# line_follower.net
KiCad netlist of a schematic drawn in EAGLE
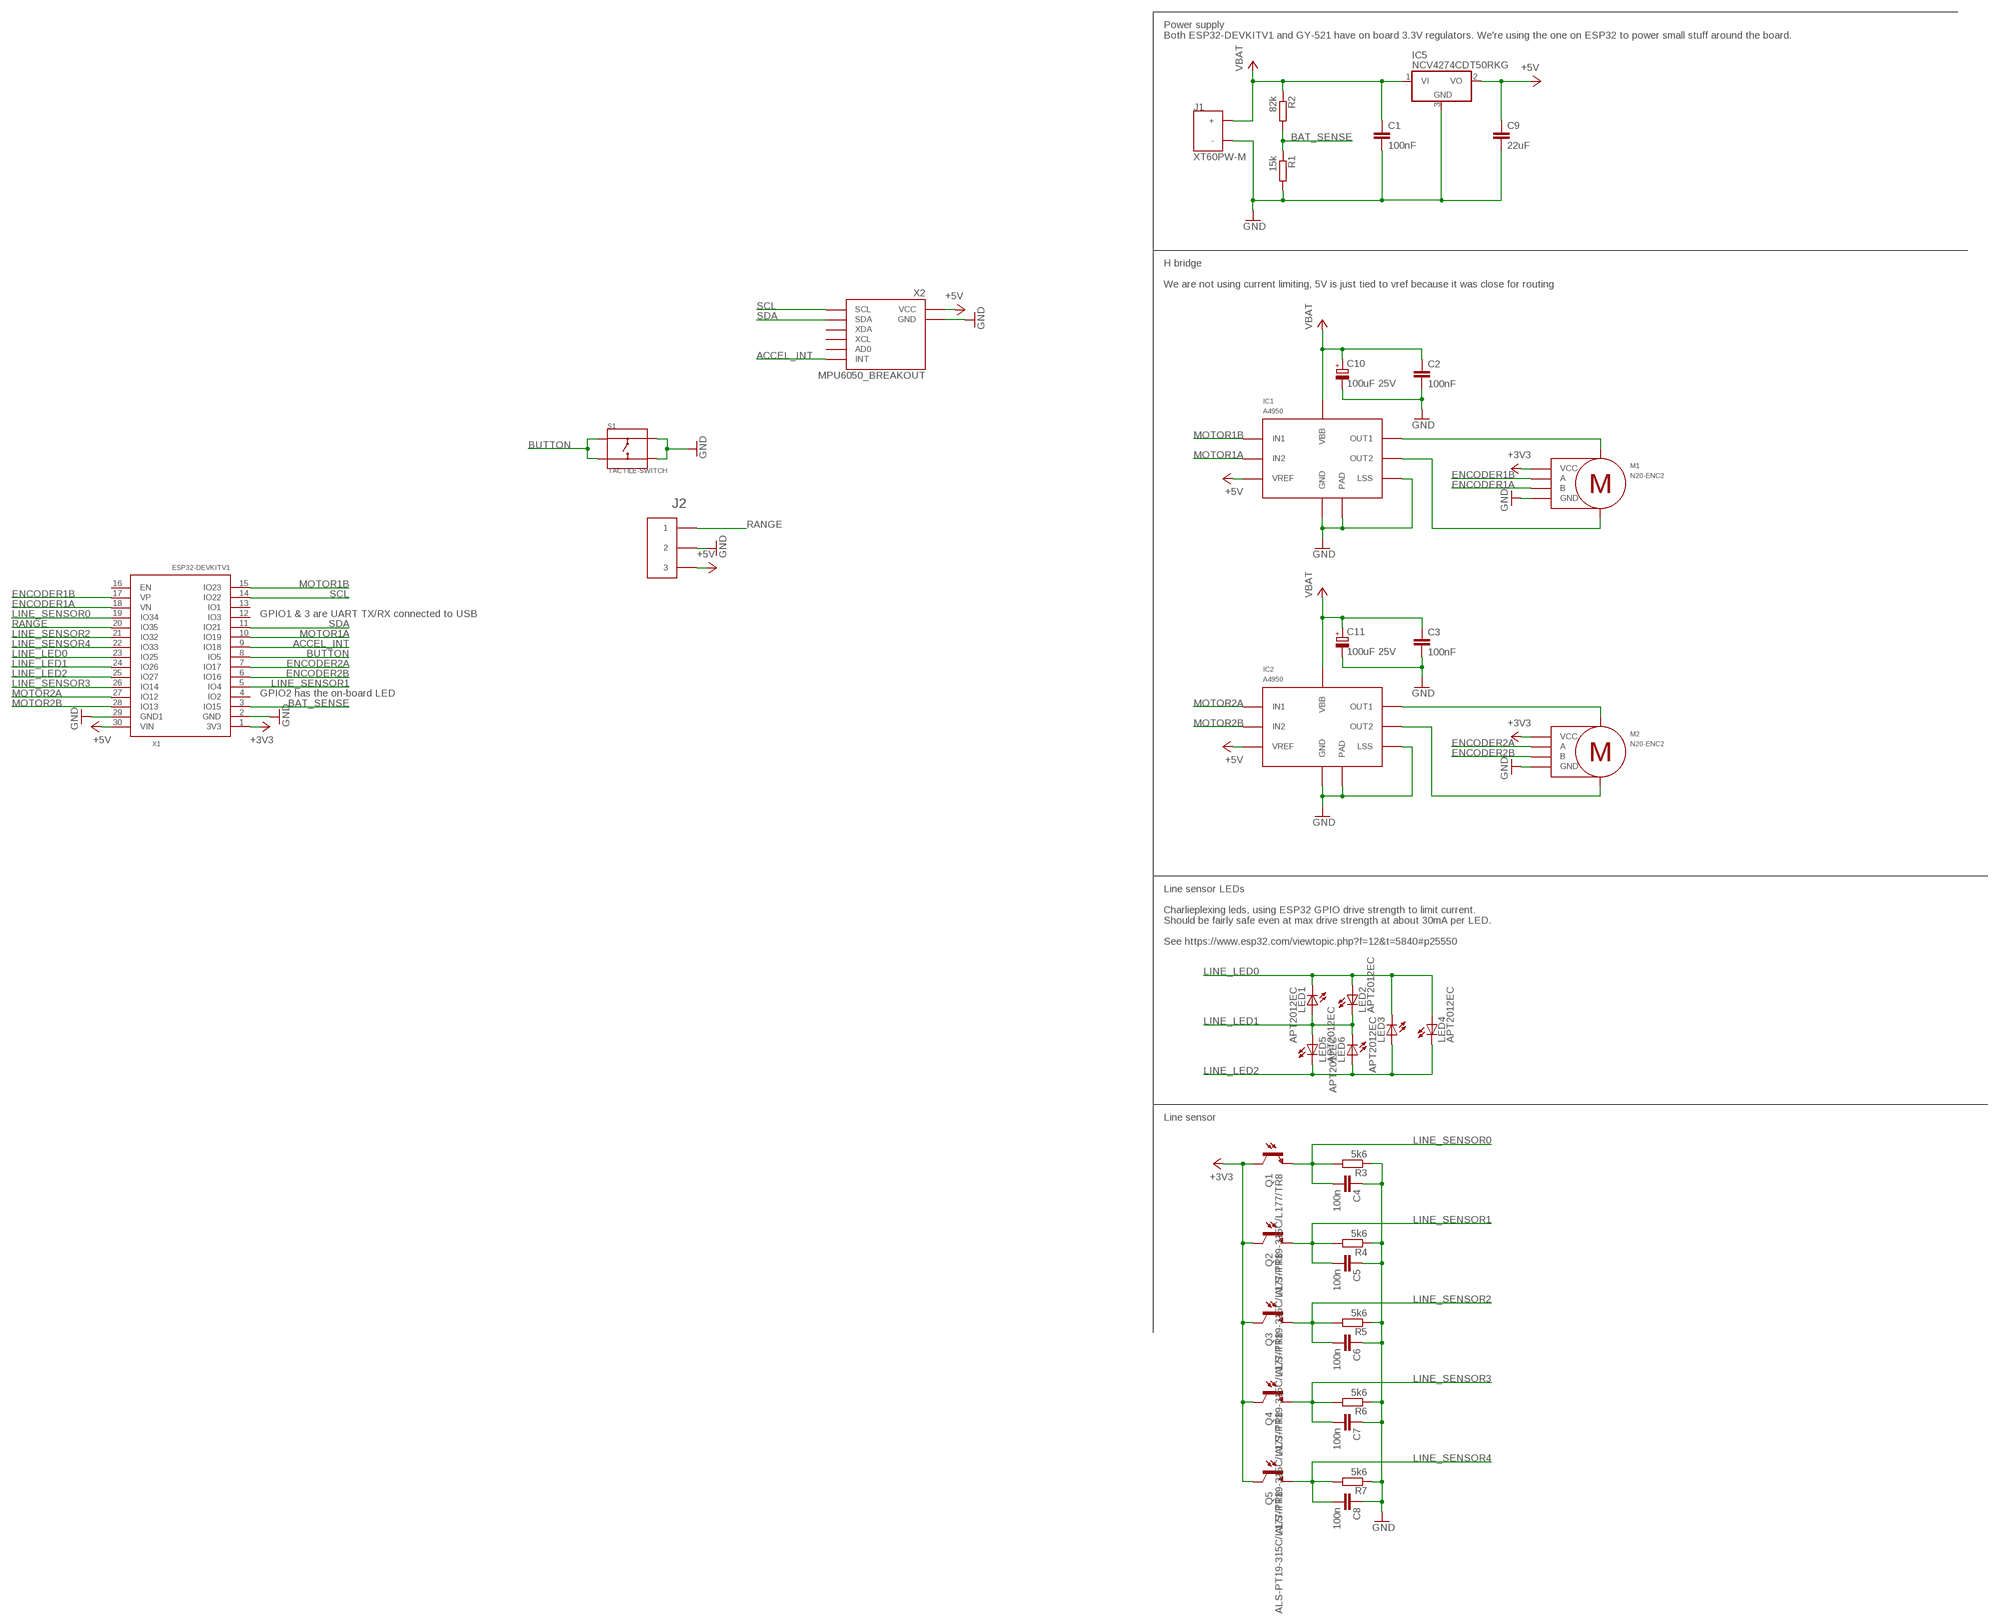
[diagram p0: schematic, sheet 1]

(export (version "E")
  (design (tool "Eeschema 10.0.6"))
  (components
    (comp (ref "C1")
      (value "100nF")
      (footprint "eagle-import:C0805")
      (libsource (lib "eagle-import") (part "C-EUC0805"))
    )
    (comp (ref "C2")
      (value "100nF")
      (footprint "eagle-import:C0805")
      (libsource (lib "eagle-import") (part "C-EUC0805"))
    )
    (comp (ref "C3")
      (value "100nF")
      (footprint "eagle-import:C0805")
      (libsource (lib "eagle-import") (part "C-EUC0805"))
    )
    (comp (ref "C4")
      (value "100n")
      (footprint "eagle-import:C0805")
      (libsource (lib "eagle-import") (part "C-EUC0805"))
    )
    (comp (ref "C5")
      (value "100n")
      (footprint "eagle-import:C0805")
      (libsource (lib "eagle-import") (part "C-EUC0805"))
    )
    (comp (ref "C6")
      (value "100n")
      (footprint "eagle-import:C0805")
      (libsource (lib "eagle-import") (part "C-EUC0805"))
    )
    (comp (ref "C7")
      (value "100n")
      (footprint "eagle-import:C0805")
      (libsource (lib "eagle-import") (part "C-EUC0805"))
    )
    (comp (ref "C8")
      (value "100n")
      (footprint "eagle-import:C0805")
      (libsource (lib "eagle-import") (part "C-EUC0805"))
    )
    (comp (ref "C9")
      (value "22uF")
      (footprint "eagle-import:C0805")
      (libsource (lib "eagle-import") (part "C-EUC0805"))
    )
    (comp (ref "C10")
      (value "100uF 25V")
      (footprint "eagle-import:UD-6,3X5,8_NICHICON")
      (libsource (lib "eagle-import") (part "CPOL-EUUD-6,3X8,8"))
    )
    (comp (ref "C11")
      (value "100uF 25V")
      (footprint "eagle-import:UD-6,3X5,8_NICHICON")
      (libsource (lib "eagle-import") (part "CPOL-EUUD-6,3X8,8"))
    )
    (comp (ref "IC1")
      (value "A4950")
      (footprint "eagle-import:SOIC8_PAD")
      (libsource (lib "eagle-import") (part "A4950"))
    )
    (comp (ref "IC2")
      (value "A4950")
      (footprint "eagle-import:SOIC8_PAD")
      (libsource (lib "eagle-import") (part "A4950"))
    )
    (comp (ref "IC5")
      (value "NCV4274CDT50RKG")
      (footprint "eagle-import:TO252")
      (libsource (lib "eagle-import") (part "78DT05"))
    )
    (comp (ref "J1")
      (value "XT60PW-M")
      (footprint "eagle-import:XT60PW-M")
      (libsource (lib "eagle-import") (part "XT60PW-M"))
    )
    (comp (ref "J2")
      (value "2.54MM_HEADER_3X1")
      (footprint "eagle-import:2.54MM_HEADER_3X1")
      (libsource (lib "eagle-import") (part "2.54MM_HEADER_3X1"))
    )
    (comp (ref "LED1")
      (value "APT2012EC")
      (footprint "eagle-import:CHIP-LED0805")
      (libsource (lib "eagle-import") (part "LEDCHIP-LED0805"))
    )
    (comp (ref "LED2")
      (value "APT2012EC")
      (footprint "eagle-import:CHIP-LED0805")
      (libsource (lib "eagle-import") (part "LEDCHIP-LED0805"))
    )
    (comp (ref "LED3")
      (value "APT2012EC")
      (footprint "eagle-import:CHIP-LED0805")
      (libsource (lib "eagle-import") (part "LEDCHIP-LED0805"))
    )
    (comp (ref "LED4")
      (value "APT2012EC")
      (footprint "eagle-import:CHIP-LED0805")
      (libsource (lib "eagle-import") (part "LEDCHIP-LED0805"))
    )
    (comp (ref "LED5")
      (value "APT2012EC")
      (footprint "eagle-import:CHIP-LED0805")
      (libsource (lib "eagle-import") (part "LEDCHIP-LED0805"))
    )
    (comp (ref "LED6")
      (value "APT2012EC")
      (footprint "eagle-import:CHIP-LED0805")
      (libsource (lib "eagle-import") (part "LEDCHIP-LED0805"))
    )
    (comp (ref "M1")
      (value "N20-ENC2")
      (footprint "eagle-import:2.54MM_HEADER_6X1")
      (libsource (lib "eagle-import") (part "N20-ENC2"))
    )
    (comp (ref "M2")
      (value "N20-ENC2")
      (footprint "eagle-import:2.54MM_HEADER_6X1")
      (libsource (lib "eagle-import") (part "N20-ENC2"))
    )
    (comp (ref "Q1")
      (value "ALS-PT19-315C/L177/TR8")
      (footprint "eagle-import:PHOTOTRANSISTOR-1.7MM")
      (libsource (lib "eagle-import") (part "ALS-PT19-315C/L177/TR8"))
    )
    (comp (ref "Q2")
      (value "ALS-PT19-315C/L177/TR8")
      (footprint "eagle-import:PHOTOTRANSISTOR-1.7MM")
      (libsource (lib "eagle-import") (part "ALS-PT19-315C/L177/TR8"))
    )
    (comp (ref "Q3")
      (value "ALS-PT19-315C/L177/TR8")
      (footprint "eagle-import:PHOTOTRANSISTOR-1.7MM")
      (libsource (lib "eagle-import") (part "ALS-PT19-315C/L177/TR8"))
    )
    (comp (ref "Q4")
      (value "ALS-PT19-315C/L177/TR8")
      (footprint "eagle-import:PHOTOTRANSISTOR-1.7MM")
      (libsource (lib "eagle-import") (part "ALS-PT19-315C/L177/TR8"))
    )
    (comp (ref "Q5")
      (value "ALS-PT19-315C/L177/TR8")
      (footprint "eagle-import:PHOTOTRANSISTOR-1.7MM")
      (libsource (lib "eagle-import") (part "ALS-PT19-315C/L177/TR8"))
    )
    (comp (ref "R1")
      (value "15k")
      (footprint "eagle-import:R0805")
      (libsource (lib "eagle-import") (part "R-EU_R0805"))
    )
    (comp (ref "R2")
      (value "82k")
      (footprint "eagle-import:R0805")
      (libsource (lib "eagle-import") (part "R-EU_R0805"))
    )
    (comp (ref "R3")
      (value "5k6")
      (footprint "eagle-import:R0805")
      (libsource (lib "eagle-import") (part "R-EU_R0805"))
    )
    (comp (ref "R4")
      (value "5k6")
      (footprint "eagle-import:R0805")
      (libsource (lib "eagle-import") (part "R-EU_R0805"))
    )
    (comp (ref "R5")
      (value "5k6")
      (footprint "eagle-import:R0805")
      (libsource (lib "eagle-import") (part "R-EU_R0805"))
    )
    (comp (ref "R6")
      (value "5k6")
      (footprint "eagle-import:R0805")
      (libsource (lib "eagle-import") (part "R-EU_R0805"))
    )
    (comp (ref "R7")
      (value "5k6")
      (footprint "eagle-import:R0805")
      (libsource (lib "eagle-import") (part "R-EU_R0805"))
    )
    (comp (ref "S1")
      (value "TACTILE-SWITCH")
      (footprint "eagle-import:SW4-SMD-4.5MM")
      (libsource (lib "eagle-import") (part "TACTILE-SWITCH"))
    )
    (comp (ref "X1")
      (value "ESP32DEVKITV1")
      (footprint "eagle-import:ESP32-DEVKITV1")
      (libsource (lib "eagle-import") (part "ESP32DEVKITV1"))
    )
    (comp (ref "X2")
      (value "MPU6050_BREAKOUT")
      (footprint "eagle-import:MPU6050_BREAKOUT")
      (libsource (lib "eagle-import") (part "MPU6050_BREAKOUT"))
    )
  )
  (nets
    (net (code "1") (name "+3V3") (class "Default")
      (node (ref "M1") (pin "P$5") (pinfunction "VCC_P$5") (pintype "power_in"))
      (node (ref "M2") (pin "P$5") (pinfunction "VCC_P$5") (pintype "power_in"))
      (node (ref "Q1") (pin "C") (pinfunction "C_C") (pintype "passive"))
      (node (ref "Q2") (pin "C") (pinfunction "C_C") (pintype "passive"))
      (node (ref "Q3") (pin "C") (pinfunction "C_C") (pintype "passive"))
      (node (ref "Q4") (pin "C") (pinfunction "C_C") (pintype "passive"))
      (node (ref "Q5") (pin "C") (pinfunction "C_C") (pintype "passive"))
      (node (ref "X1") (pin "1") (pinfunction "3V3_1") (pintype "bidirectional"))
    )
    (net (code "2") (name "+5V") (class "Default")
      (node (ref "C9") (pin "1") (pinfunction "1_1") (pintype "passive"))
      (node (ref "IC1") (pin "4") (pinfunction "VREF_4") (pintype "bidirectional"))
      (node (ref "IC2") (pin "4") (pinfunction "VREF_4") (pintype "bidirectional"))
      (node (ref "IC5") (pin "2") (pinfunction "VO_2") (pintype "passive"))
      (node (ref "J2") (pin "P$3") (pinfunction "3_P$3") (pintype "bidirectional"))
      (node (ref "X1") (pin "30") (pinfunction "VIN_30") (pintype "bidirectional"))
      (node (ref "X2") (pin "P$1") (pinfunction "VCC_P$1") (pintype "power_in"))
    )
    (net (code "3") (name "/ACCEL_INT") (class "Default")
      (node (ref "X1") (pin "9") (pinfunction "IO18_9") (pintype "bidirectional"))
      (node (ref "X2") (pin "P$8") (pinfunction "INT_P$8") (pintype "bidirectional"))
    )
    (net (code "4") (name "/BAT_SENSE") (class "Default")
      (node (ref "R1") (pin "1") (pinfunction "1_1") (pintype "passive"))
      (node (ref "R2") (pin "2") (pinfunction "2_2") (pintype "passive"))
      (node (ref "X1") (pin "3") (pinfunction "IO15_3") (pintype "bidirectional"))
    )
    (net (code "5") (name "/BUTTON") (class "Default")
      (node (ref "S1") (pin "P$1") (pinfunction "A0_P$1") (pintype "bidirectional"))
      (node (ref "S1") (pin "P$3") (pinfunction "B0_P$3") (pintype "bidirectional"))
      (node (ref "X1") (pin "8") (pinfunction "IO5_8") (pintype "bidirectional"))
    )
    (net (code "6") (name "/ENCODER1A") (class "Default")
      (node (ref "M1") (pin "P$4") (pinfunction "B_P$4") (pintype "output"))
      (node (ref "X1") (pin "18") (pinfunction "VN_18") (pintype "bidirectional"))
    )
    (net (code "7") (name "/ENCODER1B") (class "Default")
      (node (ref "M1") (pin "P$3") (pinfunction "A_P$3") (pintype "output"))
      (node (ref "X1") (pin "17") (pinfunction "VP_17") (pintype "bidirectional"))
    )
    (net (code "8") (name "/ENCODER2A") (class "Default")
      (node (ref "M2") (pin "P$3") (pinfunction "A_P$3") (pintype "output"))
      (node (ref "X1") (pin "7") (pinfunction "IO17_7") (pintype "bidirectional"))
    )
    (net (code "9") (name "/ENCODER2B") (class "Default")
      (node (ref "M2") (pin "P$4") (pinfunction "B_P$4") (pintype "output"))
      (node (ref "X1") (pin "6") (pinfunction "IO16_6") (pintype "bidirectional"))
    )
    (net (code "10") (name "/LINE_LED0") (class "Default")
      (node (ref "LED1") (pin "C") (pinfunction "C_C") (pintype "passive"))
      (node (ref "LED2") (pin "A") (pinfunction "A_A") (pintype "passive"))
      (node (ref "LED3") (pin "C") (pinfunction "C_C") (pintype "passive"))
      (node (ref "LED4") (pin "A") (pinfunction "A_A") (pintype "passive"))
      (node (ref "X1") (pin "23") (pinfunction "IO25_23") (pintype "bidirectional"))
    )
    (net (code "11") (name "/LINE_LED1") (class "Default")
      (node (ref "LED1") (pin "A") (pinfunction "A_A") (pintype "passive"))
      (node (ref "LED2") (pin "C") (pinfunction "C_C") (pintype "passive"))
      (node (ref "LED5") (pin "A") (pinfunction "A_A") (pintype "passive"))
      (node (ref "LED6") (pin "C") (pinfunction "C_C") (pintype "passive"))
      (node (ref "X1") (pin "24") (pinfunction "IO26_24") (pintype "bidirectional"))
    )
    (net (code "12") (name "/LINE_LED2") (class "Default")
      (node (ref "LED3") (pin "A") (pinfunction "A_A") (pintype "passive"))
      (node (ref "LED4") (pin "C") (pinfunction "C_C") (pintype "passive"))
      (node (ref "LED5") (pin "C") (pinfunction "C_C") (pintype "passive"))
      (node (ref "LED6") (pin "A") (pinfunction "A_A") (pintype "passive"))
      (node (ref "X1") (pin "25") (pinfunction "IO27_25") (pintype "bidirectional"))
    )
    (net (code "13") (name "/LINE_SENSOR0") (class "Default")
      (node (ref "C4") (pin "2") (pinfunction "2_2") (pintype "passive"))
      (node (ref "Q1") (pin "E") (pinfunction "E_E") (pintype "passive"))
      (node (ref "R3") (pin "2") (pinfunction "2_2") (pintype "passive"))
      (node (ref "X1") (pin "19") (pinfunction "IO34_19") (pintype "bidirectional"))
    )
    (net (code "14") (name "/LINE_SENSOR1") (class "Default")
      (node (ref "C5") (pin "2") (pinfunction "2_2") (pintype "passive"))
      (node (ref "Q2") (pin "E") (pinfunction "E_E") (pintype "passive"))
      (node (ref "R4") (pin "2") (pinfunction "2_2") (pintype "passive"))
      (node (ref "X1") (pin "5") (pinfunction "IO4_5") (pintype "bidirectional"))
    )
    (net (code "15") (name "/LINE_SENSOR2") (class "Default")
      (node (ref "C6") (pin "2") (pinfunction "2_2") (pintype "passive"))
      (node (ref "Q3") (pin "E") (pinfunction "E_E") (pintype "passive"))
      (node (ref "R5") (pin "2") (pinfunction "2_2") (pintype "passive"))
      (node (ref "X1") (pin "21") (pinfunction "IO32_21") (pintype "bidirectional"))
    )
    (net (code "16") (name "/LINE_SENSOR3") (class "Default")
      (node (ref "C7") (pin "2") (pinfunction "2_2") (pintype "passive"))
      (node (ref "Q4") (pin "E") (pinfunction "E_E") (pintype "passive"))
      (node (ref "R6") (pin "2") (pinfunction "2_2") (pintype "passive"))
      (node (ref "X1") (pin "26") (pinfunction "IO14_26") (pintype "bidirectional"))
    )
    (net (code "17") (name "/LINE_SENSOR4") (class "Default")
      (node (ref "C8") (pin "2") (pinfunction "2_2") (pintype "passive"))
      (node (ref "Q5") (pin "E") (pinfunction "E_E") (pintype "passive"))
      (node (ref "R7") (pin "2") (pinfunction "2_2") (pintype "passive"))
      (node (ref "X1") (pin "22") (pinfunction "IO33_22") (pintype "bidirectional"))
    )
    (net (code "18") (name "/MOTOR1A") (class "Default")
      (node (ref "IC1") (pin "2") (pinfunction "IN2_2") (pintype "bidirectional"))
      (node (ref "X1") (pin "10") (pinfunction "IO19_10") (pintype "bidirectional"))
    )
    (net (code "19") (name "/MOTOR1B") (class "Default")
      (node (ref "IC1") (pin "3") (pinfunction "IN1_3") (pintype "bidirectional"))
      (node (ref "X1") (pin "15") (pinfunction "IO23_15") (pintype "bidirectional"))
    )
    (net (code "20") (name "/MOTOR2A") (class "Default")
      (node (ref "IC2") (pin "3") (pinfunction "IN1_3") (pintype "bidirectional"))
      (node (ref "X1") (pin "27") (pinfunction "IO12_27") (pintype "bidirectional"))
    )
    (net (code "21") (name "/MOTOR2B") (class "Default")
      (node (ref "IC2") (pin "2") (pinfunction "IN2_2") (pintype "bidirectional"))
      (node (ref "X1") (pin "28") (pinfunction "IO13_28") (pintype "bidirectional"))
    )
    (net (code "22") (name "/RANGE") (class "Default")
      (node (ref "J2") (pin "P$1") (pinfunction "1_P$1") (pintype "bidirectional"))
      (node (ref "X1") (pin "20") (pinfunction "IO35_20") (pintype "bidirectional"))
    )
    (net (code "23") (name "/SCL") (class "Default")
      (node (ref "X1") (pin "14") (pinfunction "IO22_14") (pintype "bidirectional"))
      (node (ref "X2") (pin "P$3") (pinfunction "SCL_P$3") (pintype "bidirectional"))
    )
    (net (code "24") (name "/SDA") (class "Default")
      (node (ref "X1") (pin "11") (pinfunction "IO21_11") (pintype "bidirectional"))
      (node (ref "X2") (pin "P$4") (pinfunction "SDA_P$4") (pintype "bidirectional"))
    )
    (net (code "25") (name "GND") (class "Default")
      (node (ref "C1") (pin "2") (pinfunction "2_2") (pintype "passive"))
      (node (ref "C10") (pin "-") (pinfunction "-_-") (pintype "passive"))
      (node (ref "C11") (pin "-") (pinfunction "-_-") (pintype "passive"))
      (node (ref "C2") (pin "2") (pinfunction "2_2") (pintype "passive"))
      (node (ref "C3") (pin "2") (pinfunction "2_2") (pintype "passive"))
      (node (ref "C4") (pin "1") (pinfunction "1_1") (pintype "passive"))
      (node (ref "C5") (pin "1") (pinfunction "1_1") (pintype "passive"))
      (node (ref "C6") (pin "1") (pinfunction "1_1") (pintype "passive"))
      (node (ref "C7") (pin "1") (pinfunction "1_1") (pintype "passive"))
      (node (ref "C8") (pin "1") (pinfunction "1_1") (pintype "passive"))
      (node (ref "C9") (pin "2") (pinfunction "2_2") (pintype "passive"))
      (node (ref "IC1") (pin "1") (pinfunction "GND_1") (pintype "bidirectional"))
      (node (ref "IC1") (pin "7") (pinfunction "LSS_7") (pintype "bidirectional"))
      (node (ref "IC1") (pin "PAD") (pinfunction "PAD_PAD") (pintype "bidirectional"))
      (node (ref "IC2") (pin "1") (pinfunction "GND_1") (pintype "bidirectional"))
      (node (ref "IC2") (pin "7") (pinfunction "LSS_7") (pintype "bidirectional"))
      (node (ref "IC2") (pin "PAD") (pinfunction "PAD_PAD") (pintype "bidirectional"))
      (node (ref "IC5") (pin "3") (pinfunction "GND_3") (pintype "passive"))
      (node (ref "J1") (pin "NEG") (pinfunction "-_NEG") (pintype "passive"))
      (node (ref "J2") (pin "P$2") (pinfunction "2_P$2") (pintype "bidirectional"))
      (node (ref "M1") (pin "P$2") (pinfunction "GND_P$2") (pintype "power_in"))
      (node (ref "M2") (pin "P$2") (pinfunction "GND_P$2") (pintype "power_in"))
      (node (ref "R1") (pin "2") (pinfunction "2_2") (pintype "passive"))
      (node (ref "R3") (pin "1") (pinfunction "1_1") (pintype "passive"))
      (node (ref "R4") (pin "1") (pinfunction "1_1") (pintype "passive"))
      (node (ref "R5") (pin "1") (pinfunction "1_1") (pintype "passive"))
      (node (ref "R6") (pin "1") (pinfunction "1_1") (pintype "passive"))
      (node (ref "R7") (pin "1") (pinfunction "1_1") (pintype "passive"))
      (node (ref "S1") (pin "P$2") (pinfunction "A1_P$2") (pintype "bidirectional"))
      (node (ref "S1") (pin "P$4") (pinfunction "B1_P$4") (pintype "bidirectional"))
      (node (ref "X1") (pin "2") (pinfunction "GND_2") (pintype "bidirectional"))
      (node (ref "X1") (pin "29") (pinfunction "GND1_29") (pintype "bidirectional"))
      (node (ref "X2") (pin "P$2") (pinfunction "GND_P$2") (pintype "power_in"))
    )
    (net (code "26") (name "Net-(IC1-OUT1)") (class "Default")
      (node (ref "IC1") (pin "6") (pinfunction "OUT1_6") (pintype "bidirectional"))
      (node (ref "M1") (pin "P$1") (pinfunction "M+_P$1") (pintype "input"))
    )
    (net (code "27") (name "Net-(IC1-OUT2)") (class "Default")
      (node (ref "IC1") (pin "8") (pinfunction "OUT2_8") (pintype "bidirectional"))
      (node (ref "M1") (pin "P$6") (pinfunction "M-_P$6") (pintype "input"))
    )
    (net (code "28") (name "Net-(IC2-OUT1)") (class "Default")
      (node (ref "IC2") (pin "6") (pinfunction "OUT1_6") (pintype "bidirectional"))
      (node (ref "M2") (pin "P$1") (pinfunction "M+_P$1") (pintype "input"))
    )
    (net (code "29") (name "Net-(IC2-OUT2)") (class "Default")
      (node (ref "IC2") (pin "8") (pinfunction "OUT2_8") (pintype "bidirectional"))
      (node (ref "M2") (pin "P$6") (pinfunction "M-_P$6") (pintype "input"))
    )
    (net (code "30") (name "VBAT") (class "Default")
      (node (ref "C1") (pin "1") (pinfunction "1_1") (pintype "passive"))
      (node (ref "C10") (pin "+") (pinfunction "+_+") (pintype "passive"))
      (node (ref "C11") (pin "+") (pinfunction "+_+") (pintype "passive"))
      (node (ref "C2") (pin "1") (pinfunction "1_1") (pintype "passive"))
      (node (ref "C3") (pin "1") (pinfunction "1_1") (pintype "passive"))
      (node (ref "IC1") (pin "5") (pinfunction "VBB_5") (pintype "bidirectional"))
      (node (ref "IC2") (pin "5") (pinfunction "VBB_5") (pintype "bidirectional"))
      (node (ref "IC5") (pin "1") (pinfunction "VI_1") (pintype "input"))
      (node (ref "J1") (pin "POS") (pinfunction "+_POS") (pintype "passive"))
      (node (ref "R2") (pin "1") (pinfunction "1_1") (pintype "passive"))
    )
    (net (code "31") (name "unconnected-(X1-EN-Pad16)") (class "Default")
      (node (ref "X1") (pin "16") (pinfunction "EN_16") (pintype "bidirectional"))
    )
    (net (code "32") (name "unconnected-(X1-IO1-Pad13)") (class "Default")
      (node (ref "X1") (pin "13") (pinfunction "IO1_13") (pintype "bidirectional"))
    )
    (net (code "33") (name "unconnected-(X1-IO2-Pad4)") (class "Default")
      (node (ref "X1") (pin "4") (pinfunction "IO2_4") (pintype "bidirectional"))
    )
    (net (code "34") (name "unconnected-(X1-IO3-Pad12)") (class "Default")
      (node (ref "X1") (pin "12") (pinfunction "IO3_12") (pintype "bidirectional"))
    )
    (net (code "35") (name "unconnected-(X2-AD0-PadP$7)") (class "Default")
      (node (ref "X2") (pin "P$7") (pinfunction "AD0_P$7") (pintype "tri_state"))
    )
    (net (code "36") (name "unconnected-(X2-XCL-PadP$5)") (class "Default")
      (node (ref "X2") (pin "P$5") (pinfunction "XCL_P$5") (pintype "bidirectional"))
    )
    (net (code "37") (name "unconnected-(X2-XDA-PadP$6)") (class "Default")
      (node (ref "X2") (pin "P$6") (pinfunction "XDA_P$6") (pintype "bidirectional"))
    )
  )
)
